# Sheet1.net
KiCad netlist of a schematic drawn in Altium Designer
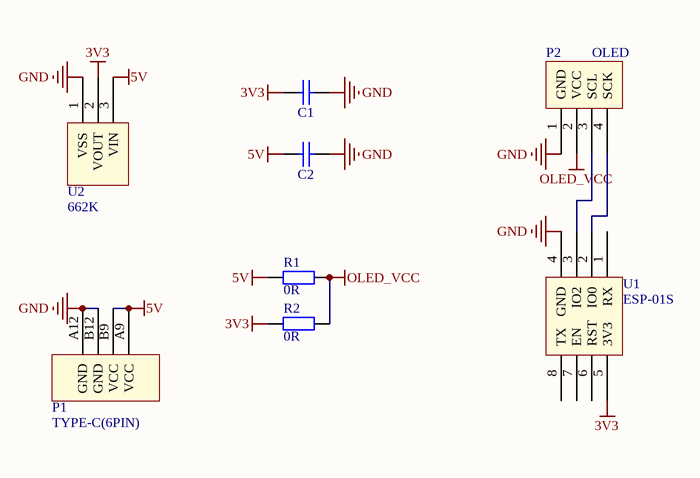
[diagram p0: Sheet1.SchDoc]

(export (version "E")
  (design (tool "Eeschema 10.0.6"))
  (components
    (comp (ref "C1")
      (value "~")
      (footprint "C 0805")
      (description "无极性电容")
      (libsource (lib "Schlib1") (part "Cap1"))
    )
    (comp (ref "C2")
      (value "~")
      (footprint "C 0805")
      (description "无极性电容")
      (libsource (lib "Schlib1") (part "Cap1"))
    )
    (comp (ref "P1")
      (value "TYPE-C(6PIN)")
      (footprint "USB-C/S_C")
      (libsource (lib "Schlib1") (part "TYPE-C(6PIN)"))
    )
    (comp (ref "P2") (value "OLED") (footprint "P4") (libsource (lib "Schlib1") (part "OLED")))
    (comp (ref "R1")
      (value "0R")
      (footprint "R 0805")
      (description "电阻")
      (libsource (lib "Schlib1") (part "Res"))
    )
    (comp (ref "R2")
      (value "0R")
      (footprint "R 0805")
      (description "电阻")
      (libsource (lib "Schlib1") (part "Res"))
    )
    (comp (ref "U1")
      (value "ESP-01S")
      (footprint "ESP-01&01S Module")
      (libsource (lib "Schlib1") (part "ESP-01S"))
    )
    (comp (ref "U2") (value "662K") (footprint "SOT23-3N") (libsource (lib "Schlib1") (part "662K")))
  )
  (nets
    (net (code "1") (name "3V3") (class "Default")
      (node (ref "C1") (pin "1") (pinfunction "1_1") (pintype "passive"))
      (node (ref "R2") (pin "2") (pinfunction "2_2") (pintype "passive"))
      (node (ref "U1") (pin "5") (pinfunction "3V3_5") (pintype "passive"))
      (node (ref "U2") (pin "2") (pinfunction "VOUT_2") (pintype "passive"))
    )
    (net (code "2") (name "5V") (class "Default")
      (node (ref "C2") (pin "1") (pinfunction "1_1") (pintype "passive"))
      (node (ref "P1") (pin "A9") (pinfunction "VCC_A9") (pintype "passive"))
      (node (ref "P1") (pin "B9") (pinfunction "VCC_B9") (pintype "passive"))
      (node (ref "R1") (pin "2") (pinfunction "2_2") (pintype "passive"))
      (node (ref "U2") (pin "3") (pinfunction "VIN_3") (pintype "passive"))
    )
    (net (code "3") (name "GND") (class "Default")
      (node (ref "C1") (pin "2") (pinfunction "2_2") (pintype "passive"))
      (node (ref "C2") (pin "2") (pinfunction "2_2") (pintype "passive"))
      (node (ref "P1") (pin "A12") (pinfunction "GND_A12") (pintype "passive"))
      (node (ref "P1") (pin "B12") (pinfunction "GND_B12") (pintype "passive"))
      (node (ref "P2") (pin "1") (pinfunction "GND_1") (pintype "passive"))
      (node (ref "U1") (pin "4") (pinfunction "GND_4") (pintype "passive"))
      (node (ref "U2") (pin "1") (pinfunction "VSS_1") (pintype "passive"))
    )
    (net (code "4") (name "Net-(P2-SCK)") (class "Default")
      (node (ref "P2") (pin "4") (pinfunction "SCK_4") (pintype "passive"))
      (node (ref "U1") (pin "2") (pinfunction "IO0_2") (pintype "passive"))
    )
    (net (code "5") (name "Net-(P2-SCL)") (class "Default")
      (node (ref "P2") (pin "3") (pinfunction "SCL_3") (pintype "passive"))
      (node (ref "U1") (pin "3") (pinfunction "IO2_3") (pintype "passive"))
    )
    (net (code "6") (name "OLED_VCC") (class "Default")
      (node (ref "P2") (pin "2") (pinfunction "VCC_2") (pintype "passive"))
      (node (ref "R1") (pin "1") (pinfunction "1_1") (pintype "passive"))
      (node (ref "R2") (pin "1") (pinfunction "1_1") (pintype "passive"))
    )
    (net (code "7") (name "unconnected-(U1-EN-Pad7)") (class "Default")
      (node (ref "U1") (pin "7") (pinfunction "EN_7") (pintype "passive"))
    )
    (net (code "8") (name "unconnected-(U1-RST-Pad6)") (class "Default")
      (node (ref "U1") (pin "6") (pinfunction "RST_6") (pintype "passive"))
    )
    (net (code "9") (name "unconnected-(U1-RX-Pad1)") (class "Default")
      (node (ref "U1") (pin "1") (pinfunction "RX_1") (pintype "passive"))
    )
    (net (code "10") (name "unconnected-(U1-TX-Pad8)") (class "Default")
      (node (ref "U1") (pin "8") (pinfunction "TX_8") (pintype "passive"))
    )
  )
)
